# shield.net
KiCad netlist of a schematic drawn in EAGLE
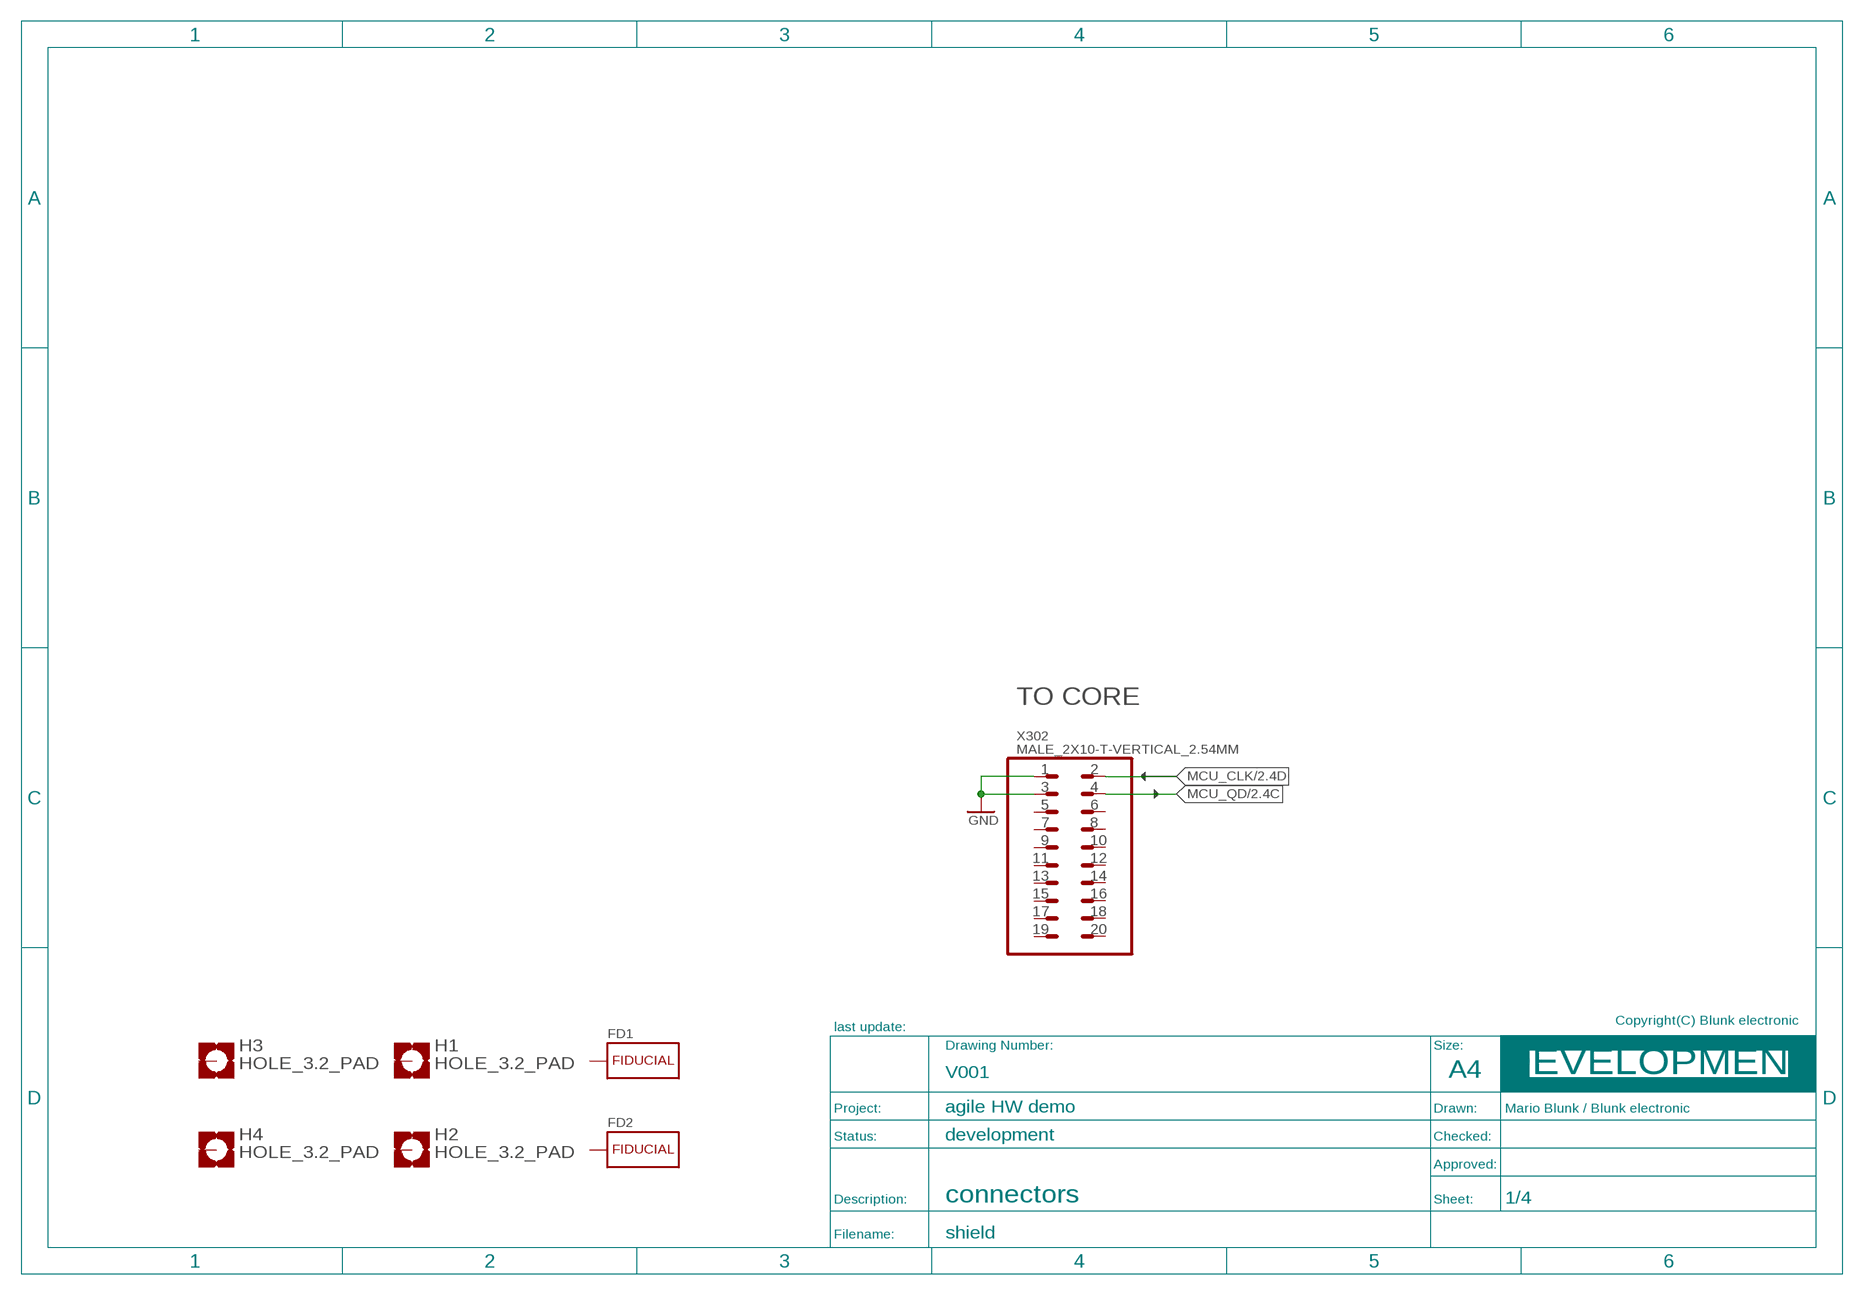
[diagram p0: schematic, sheet 1]
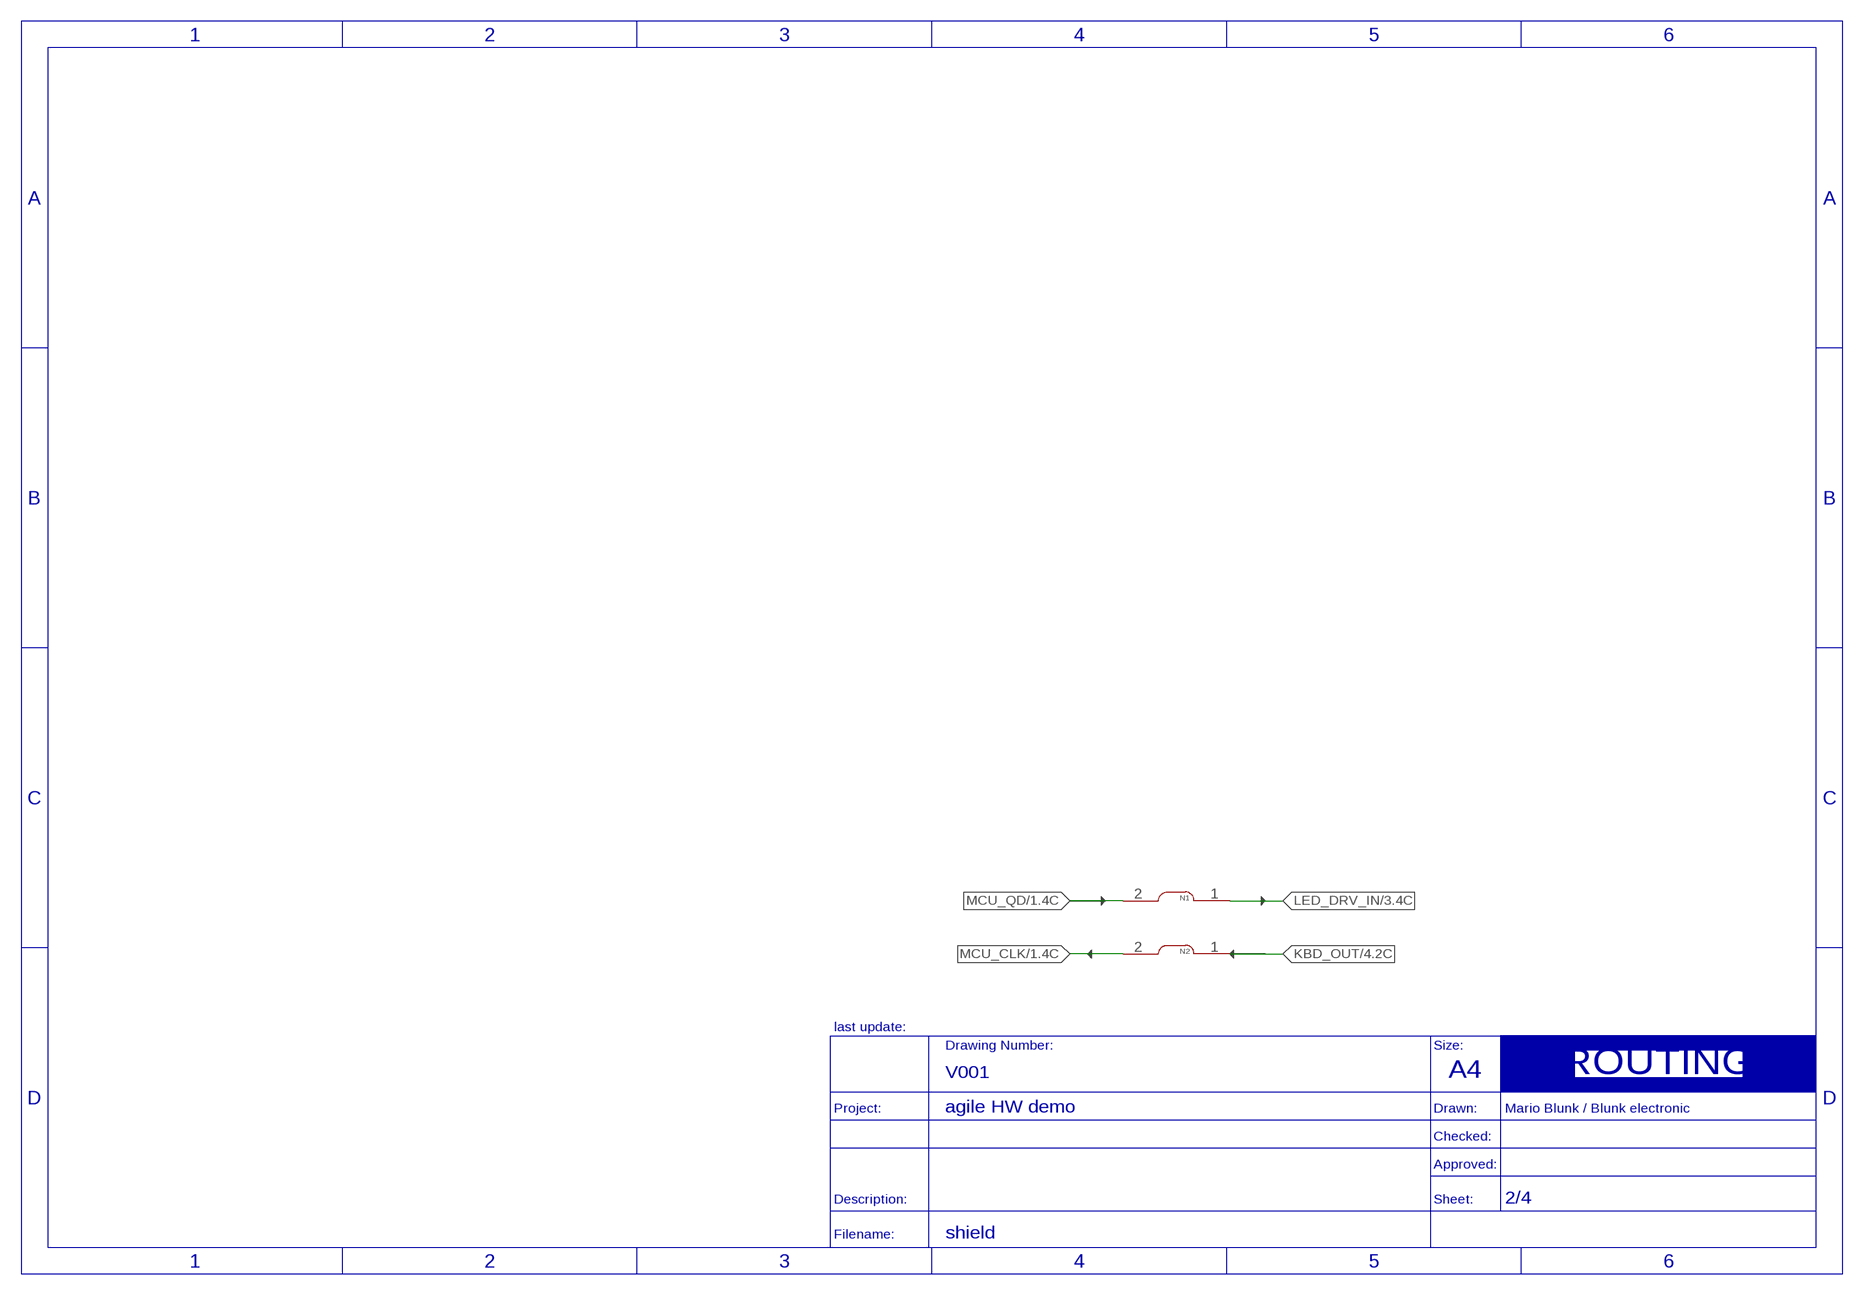
[diagram p1: schematic, sheet 2]
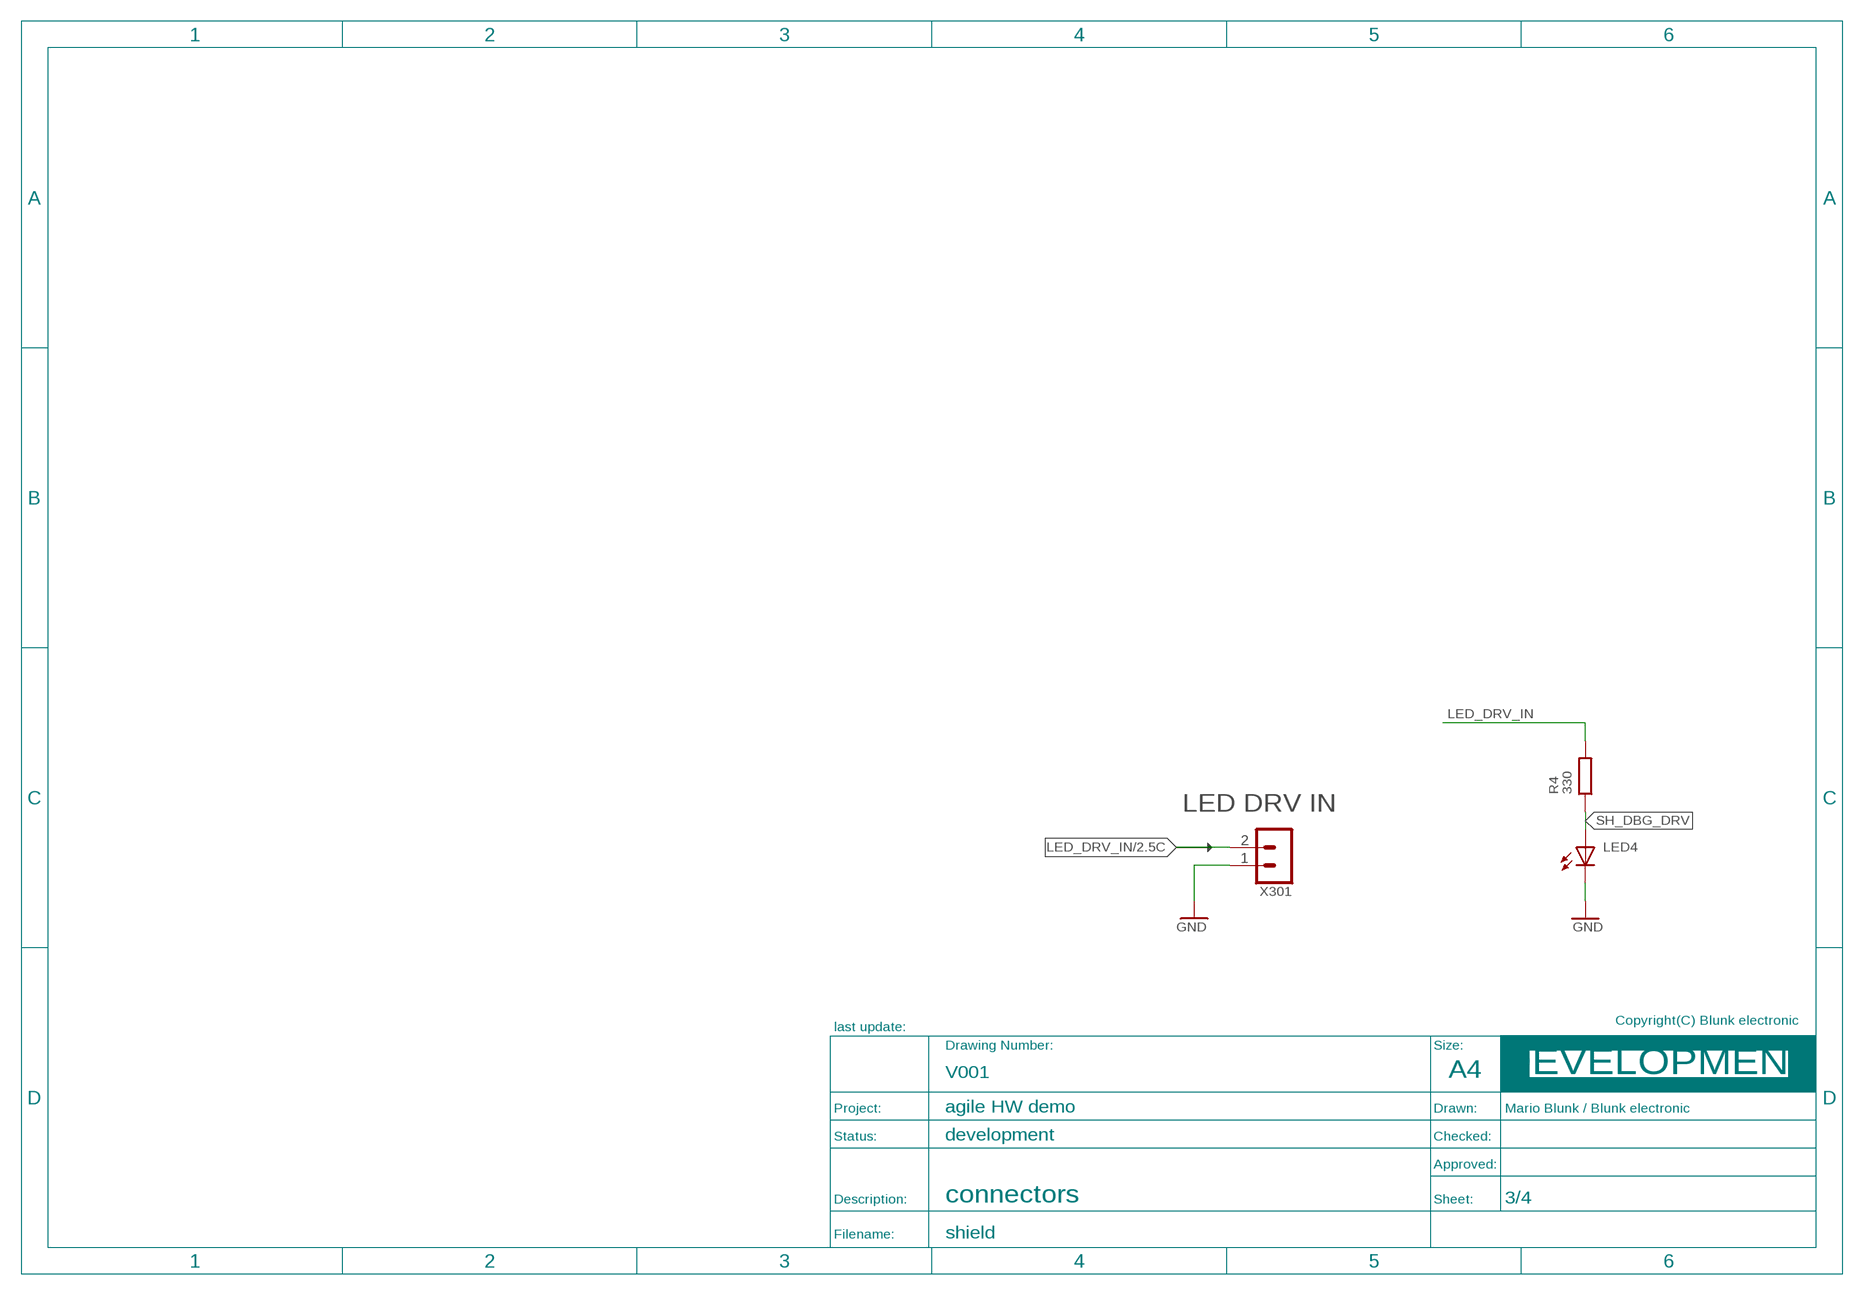
[diagram p2: schematic, sheet 3]
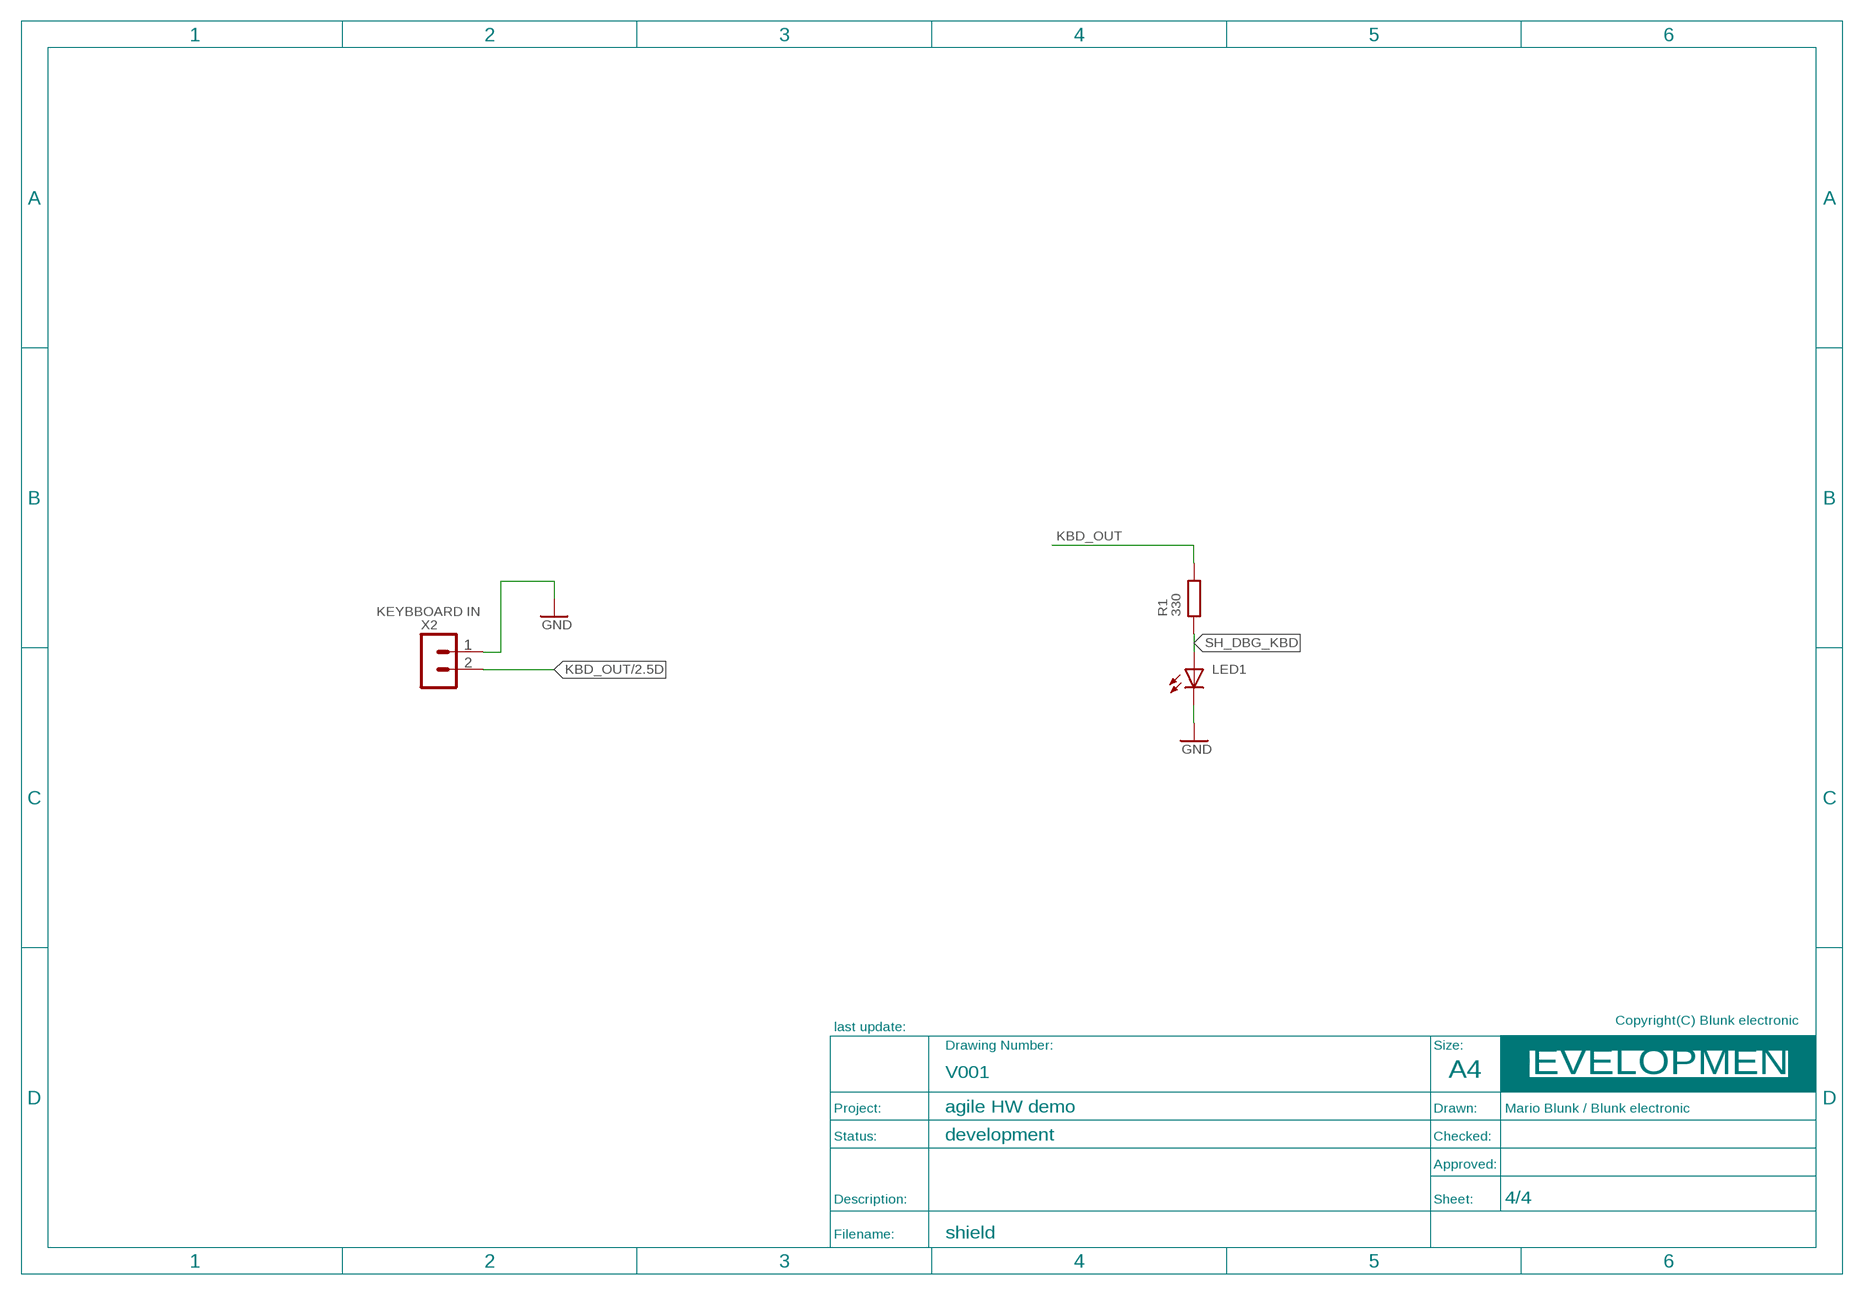
[diagram p3: schematic, sheet 4]

(export (version "E")
  (design (tool "Eeschema 10.0.6"))
  (components
    (comp (ref "LED1")
      (value "LED_S_0805")
      (footprint "eagle-import:S_0805")
      (fields (field (name "FUNCTION") "BOTTON PRESSED"))
      (libsource (lib "eagle-import") (part "LED_S_0805"))
    )
    (comp (ref "R1")
      (value "330")
      (footprint "eagle-import:S_0805")
      (libsource (lib "eagle-import") (part "R_S_0805"))
    )
    (comp (ref "X2")
      (value "MALE_2X1-T-VERTICAL")
      (footprint "eagle-import:T_MALE_2X1_VERTICAL_PITCH_2MM54")
      (fields (field (name "FUNCTION") "KEYBBOARD IN"))
      (libsource (lib "eagle-import") (part "MALE_2X1-T-VERTICAL"))
    )
    (comp (ref "N1")
      (value "NET_CHANGER-S-0.3MM")
      (footprint "eagle-import:S_NET_CHANGER_0.3MM")
      (libsource (lib "eagle-import") (part "NET_CHANGER-S-0.3MM"))
    )
    (comp (ref "N2")
      (value "NET_CHANGER-S-0.15MM")
      (footprint "eagle-import:S_NET_CHANGER_0.15MM")
      (libsource (lib "eagle-import") (part "NET_CHANGER-S-0.15MM"))
    )
    (comp (ref "LED4")
      (value "LED_S_0805")
      (footprint "eagle-import:S_0805")
      (fields (field (name "FUNCTION") "LIGHT ACTIVE"))
      (libsource (lib "eagle-import") (part "LED_S_0805"))
    )
    (comp (ref "R4")
      (value "330")
      (footprint "eagle-import:S_0805")
      (libsource (lib "eagle-import") (part "R_S_0805"))
    )
    (comp (ref "X301")
      (value "MALE_2X1-T-VERTICAL")
      (footprint "eagle-import:T_MALE_2X1_VERTICAL_PITCH_2MM54")
      (fields (field (name "FUNCTION") "LED DRV IN"))
      (libsource (lib "eagle-import") (part "MALE_2X1-T-VERTICAL"))
    )
    (comp (ref "FD1")
      (value "FIDUCIAL_CROSSHAIR")
      (footprint "eagle-import:CROSSHAIR")
      (libsource (lib "eagle-import") (part "FIDUCIAL_CROSSHAIR"))
    )
    (comp (ref "FD2")
      (value "FIDUCIAL_CROSSHAIR")
      (footprint "eagle-import:CROSSHAIR")
      (libsource (lib "eagle-import") (part "FIDUCIAL_CROSSHAIR"))
    )
    (comp (ref "H1")
      (value "HOLE_3.2_PAD")
      (footprint "eagle-import:3.2_PAD")
      (libsource (lib "eagle-import") (part "HOLE_3.2_PAD"))
    )
    (comp (ref "H2")
      (value "HOLE_3.2_PAD")
      (footprint "eagle-import:3.2_PAD")
      (libsource (lib "eagle-import") (part "HOLE_3.2_PAD"))
    )
    (comp (ref "H3")
      (value "HOLE_3.2_PAD")
      (footprint "eagle-import:3.2_PAD")
      (libsource (lib "eagle-import") (part "HOLE_3.2_PAD"))
    )
    (comp (ref "H4")
      (value "HOLE_3.2_PAD")
      (footprint "eagle-import:3.2_PAD")
      (libsource (lib "eagle-import") (part "HOLE_3.2_PAD"))
    )
    (comp (ref "X302")
      (value "MALE_2X10-T-VERTICAL_2.54MM")
      (footprint "eagle-import:T_MALE_2X10_VERTICAL_GRID_2.54MM")
      (fields (field (name "FUNCTION") "TO CORE"))
      (libsource (lib "eagle-import") (part "MALE_2X10-T-VERTICAL_2.54MM"))
    )
  )
  (nets
    (net (code "1") (name "GND") (class "Default")
      (node (ref "LED1") (pin "C") (pinfunction "C_C") (pintype "passive"))
      (node (ref "LED4") (pin "C") (pinfunction "C_C") (pintype "passive"))
      (node (ref "X2") (pin "1") (pinfunction "1_1") (pintype "passive"))
      (node (ref "X301") (pin "1") (pinfunction "1_1") (pintype "passive"))
      (node (ref "X302") (pin "1") (pinfunction "1_1") (pintype "passive"))
      (node (ref "X302") (pin "3") (pinfunction "3_3") (pintype "passive"))
    )
    (net (code "2") (name "KBD_OUT") (class "Default")
      (node (ref "N2") (pin "1") (pinfunction "1_1") (pintype "passive"))
      (node (ref "R1") (pin "2") (pinfunction "2_2") (pintype "passive"))
      (node (ref "X2") (pin "2") (pinfunction "2_2") (pintype "passive"))
    )
    (net (code "3") (name "LED_DRV_IN") (class "Default")
      (node (ref "N1") (pin "1") (pinfunction "1_1") (pintype "passive"))
      (node (ref "R4") (pin "2") (pinfunction "2_2") (pintype "passive"))
      (node (ref "X301") (pin "2") (pinfunction "2_2") (pintype "passive"))
    )
    (net (code "4") (name "MCU_CLK") (class "Default")
      (node (ref "N2") (pin "2") (pinfunction "2_2") (pintype "passive"))
      (node (ref "X302") (pin "2") (pinfunction "2_2") (pintype "passive"))
    )
    (net (code "5") (name "MCU_QD") (class "Default")
      (node (ref "N1") (pin "2") (pinfunction "2_2") (pintype "passive"))
      (node (ref "X302") (pin "4") (pinfunction "4_4") (pintype "passive"))
    )
    (net (code "6") (name "SH_DBG_DRV") (class "Default")
      (node (ref "LED4") (pin "A") (pinfunction "A_A") (pintype "passive"))
      (node (ref "R4") (pin "1") (pinfunction "1_1") (pintype "passive"))
    )
    (net (code "7") (name "SH_DBG_KBD") (class "Default")
      (node (ref "LED1") (pin "A") (pinfunction "A_A") (pintype "passive"))
      (node (ref "R1") (pin "1") (pinfunction "1_1") (pintype "passive"))
    )
    (net (code "8") (name "unconnected-(FD1-NC-Pad1)") (class "Default")
      (node (ref "FD1") (pin "1") (pinfunction "NC_1") (pintype "no_connect"))
    )
    (net (code "9") (name "unconnected-(FD2-NC-Pad1)") (class "Default")
      (node (ref "FD2") (pin "1") (pinfunction "NC_1") (pintype "no_connect"))
    )
    (net (code "10") (name "unconnected-(H1-MOUNT-PadH1)") (class "Default")
      (node (ref "H1") (pin "H1") (pinfunction "MOUNT_H1") (pintype "passive"))
    )
    (net (code "11") (name "unconnected-(H2-MOUNT-PadH1)") (class "Default")
      (node (ref "H2") (pin "H1") (pinfunction "MOUNT_H1") (pintype "passive"))
    )
    (net (code "12") (name "unconnected-(H3-MOUNT-PadH1)") (class "Default")
      (node (ref "H3") (pin "H1") (pinfunction "MOUNT_H1") (pintype "passive"))
    )
    (net (code "13") (name "unconnected-(H4-MOUNT-PadH1)") (class "Default")
      (node (ref "H4") (pin "H1") (pinfunction "MOUNT_H1") (pintype "passive"))
    )
    (net (code "14") (name "unconnected-(X302-Pad5)") (class "Default")
      (node (ref "X302") (pin "5") (pinfunction "5_5") (pintype "passive"))
    )
    (net (code "15") (name "unconnected-(X302-Pad6)") (class "Default")
      (node (ref "X302") (pin "6") (pinfunction "6_6") (pintype "passive"))
    )
    (net (code "16") (name "unconnected-(X302-Pad7)") (class "Default")
      (node (ref "X302") (pin "7") (pinfunction "7_7") (pintype "passive"))
    )
    (net (code "17") (name "unconnected-(X302-Pad8)") (class "Default")
      (node (ref "X302") (pin "8") (pinfunction "8_8") (pintype "passive"))
    )
    (net (code "18") (name "unconnected-(X302-Pad9)") (class "Default")
      (node (ref "X302") (pin "9") (pinfunction "9_9") (pintype "passive"))
    )
    (net (code "19") (name "unconnected-(X302-Pad10)") (class "Default")
      (node (ref "X302") (pin "10") (pinfunction "10_10") (pintype "passive"))
    )
    (net (code "20") (name "unconnected-(X302-Pad11)") (class "Default")
      (node (ref "X302") (pin "11") (pinfunction "11_11") (pintype "passive"))
    )
    (net (code "21") (name "unconnected-(X302-Pad12)") (class "Default")
      (node (ref "X302") (pin "12") (pinfunction "12_12") (pintype "passive"))
    )
    (net (code "22") (name "unconnected-(X302-Pad13)") (class "Default")
      (node (ref "X302") (pin "13") (pinfunction "13_13") (pintype "passive"))
    )
    (net (code "23") (name "unconnected-(X302-Pad14)") (class "Default")
      (node (ref "X302") (pin "14") (pinfunction "14_14") (pintype "passive"))
    )
    (net (code "24") (name "unconnected-(X302-Pad15)") (class "Default")
      (node (ref "X302") (pin "15") (pinfunction "15_15") (pintype "passive"))
    )
    (net (code "25") (name "unconnected-(X302-Pad16)") (class "Default")
      (node (ref "X302") (pin "16") (pinfunction "16_16") (pintype "passive"))
    )
    (net (code "26") (name "unconnected-(X302-Pad17)") (class "Default")
      (node (ref "X302") (pin "17") (pinfunction "17_17") (pintype "passive"))
    )
    (net (code "27") (name "unconnected-(X302-Pad18)") (class "Default")
      (node (ref "X302") (pin "18") (pinfunction "18_18") (pintype "passive"))
    )
    (net (code "28") (name "unconnected-(X302-Pad19)") (class "Default")
      (node (ref "X302") (pin "19") (pinfunction "19_19") (pintype "passive"))
    )
    (net (code "29") (name "unconnected-(X302-Pad20)") (class "Default")
      (node (ref "X302") (pin "20") (pinfunction "20_20") (pintype "passive"))
    )
  )
)
